# M228pnames.net
KiCad netlist of a schematic drawn in EAGLE
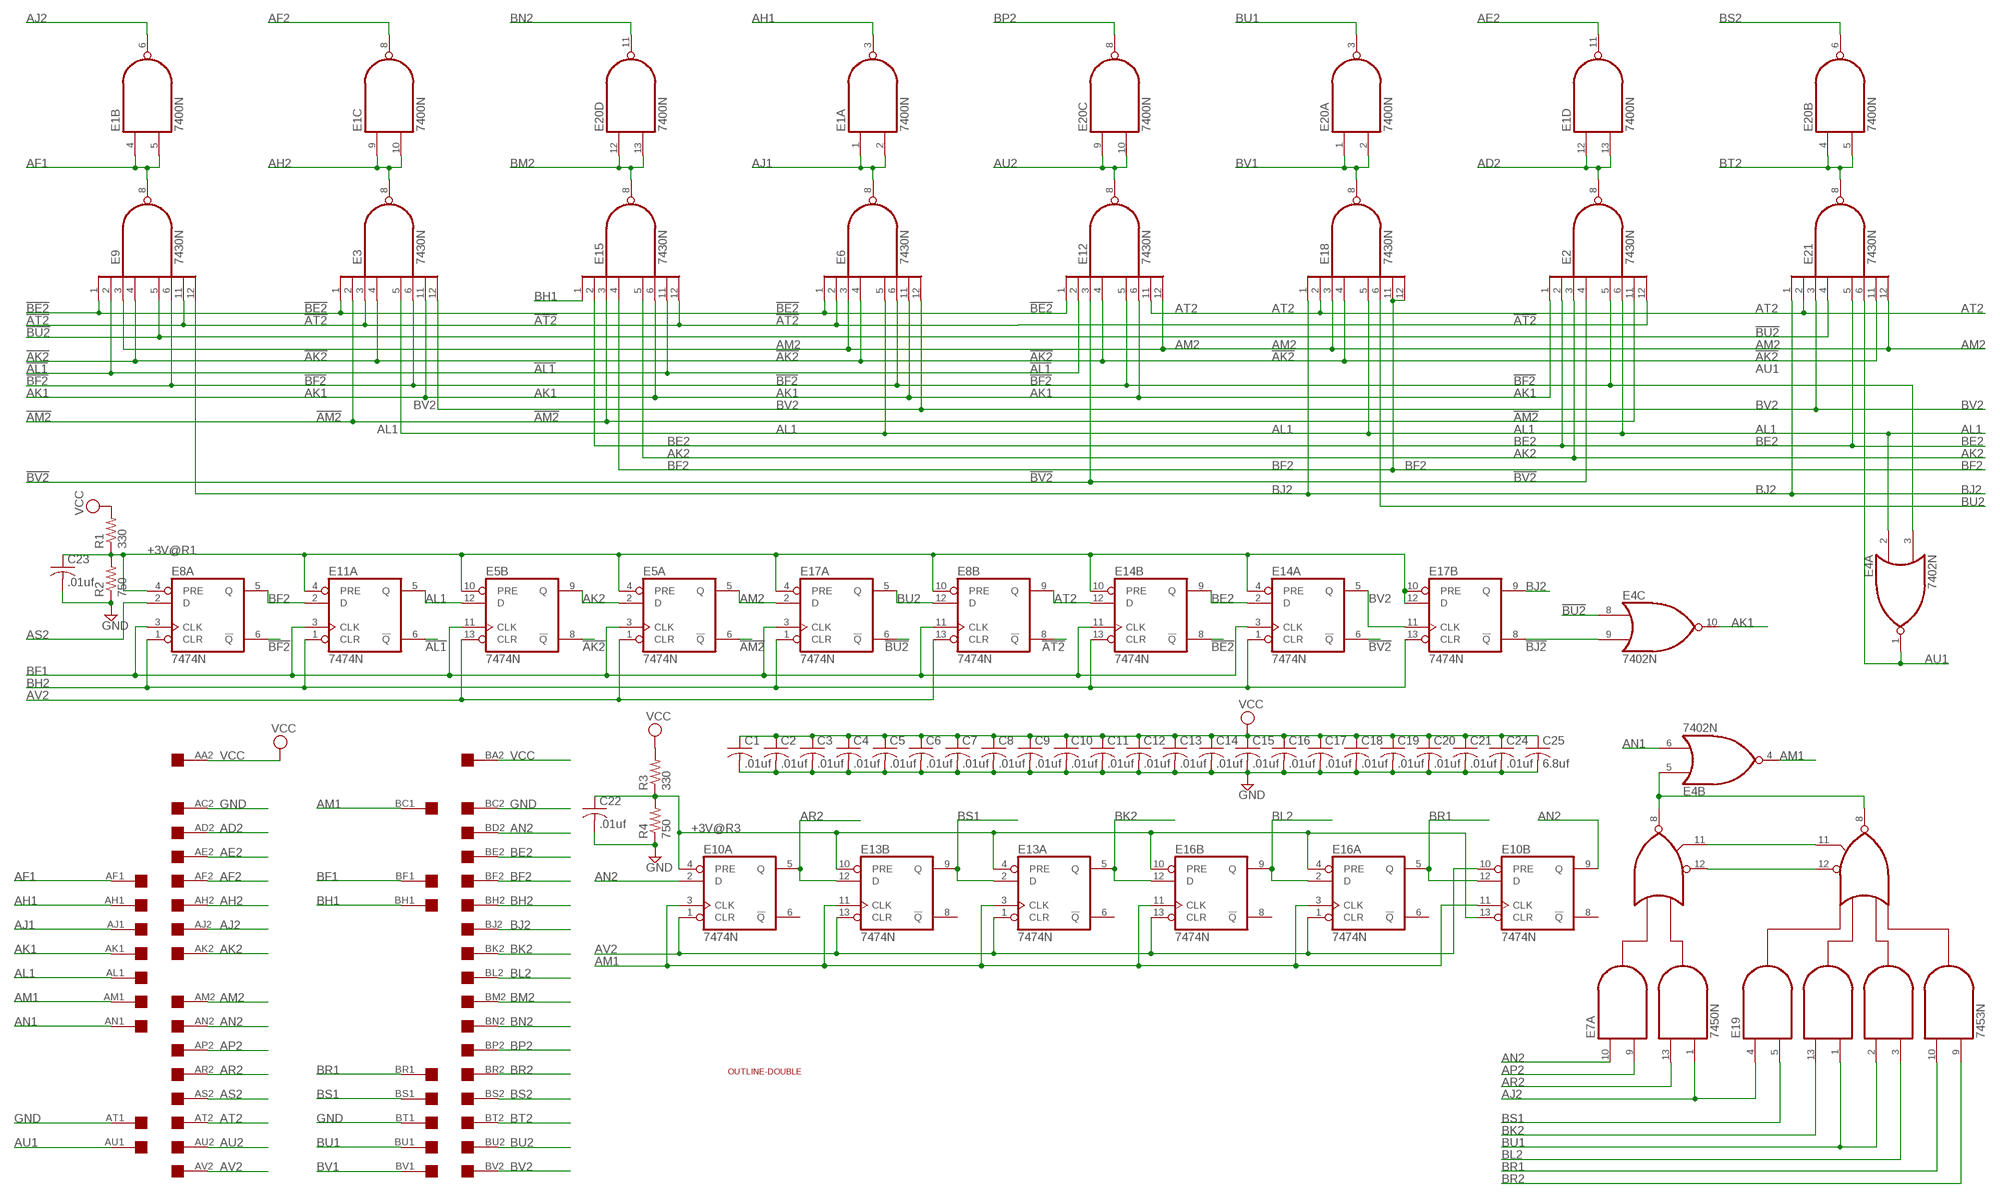
[diagram p0: schematic, sheet 1]

(export (version "E")
  (design (tool "Eeschema 10.0.6"))
  (components
    (comp (ref "C1")
      (value ".01uf")
      (footprint "eagle-import:C050-025X075")
      (libsource (lib "eagle-import") (part "C-US050-025X075"))
    )
    (comp (ref "C2")
      (value ".01uf")
      (footprint "eagle-import:C050-025X075")
      (libsource (lib "eagle-import") (part "C-US050-025X075"))
    )
    (comp (ref "C3")
      (value ".01uf")
      (footprint "eagle-import:C050-025X075")
      (libsource (lib "eagle-import") (part "C-US050-025X075"))
    )
    (comp (ref "C4")
      (value ".01uf")
      (footprint "eagle-import:C050-025X075")
      (libsource (lib "eagle-import") (part "C-US050-025X075"))
    )
    (comp (ref "C5")
      (value ".01uf")
      (footprint "eagle-import:C050-025X075")
      (libsource (lib "eagle-import") (part "C-US050-025X075"))
    )
    (comp (ref "C6")
      (value ".01uf")
      (footprint "eagle-import:C050-025X075")
      (libsource (lib "eagle-import") (part "C-US050-025X075"))
    )
    (comp (ref "C7")
      (value ".01uf")
      (footprint "eagle-import:C050-025X075")
      (libsource (lib "eagle-import") (part "C-US050-025X075"))
    )
    (comp (ref "C8")
      (value ".01uf")
      (footprint "eagle-import:C050-025X075")
      (libsource (lib "eagle-import") (part "C-US050-025X075"))
    )
    (comp (ref "C9")
      (value ".01uf")
      (footprint "eagle-import:C050-025X075")
      (libsource (lib "eagle-import") (part "C-US050-025X075"))
    )
    (comp (ref "C10")
      (value ".01uf")
      (footprint "eagle-import:C050-025X075")
      (libsource (lib "eagle-import") (part "C-US050-025X075"))
    )
    (comp (ref "C11")
      (value ".01uf")
      (footprint "eagle-import:C050-025X075")
      (libsource (lib "eagle-import") (part "C-US050-025X075"))
    )
    (comp (ref "C12")
      (value ".01uf")
      (footprint "eagle-import:C050-025X075")
      (libsource (lib "eagle-import") (part "C-US050-025X075"))
    )
    (comp (ref "C13")
      (value ".01uf")
      (footprint "eagle-import:C050-025X075")
      (libsource (lib "eagle-import") (part "C-US050-025X075"))
    )
    (comp (ref "C14")
      (value ".01uf")
      (footprint "eagle-import:C050-025X075")
      (libsource (lib "eagle-import") (part "C-US050-025X075"))
    )
    (comp (ref "C15")
      (value ".01uf")
      (footprint "eagle-import:C050-025X075")
      (libsource (lib "eagle-import") (part "C-US050-025X075"))
    )
    (comp (ref "C16")
      (value ".01uf")
      (footprint "eagle-import:C050-025X075")
      (libsource (lib "eagle-import") (part "C-US050-025X075"))
    )
    (comp (ref "C17")
      (value ".01uf")
      (footprint "eagle-import:C050-025X075")
      (libsource (lib "eagle-import") (part "C-US050-025X075"))
    )
    (comp (ref "C18")
      (value ".01uf")
      (footprint "eagle-import:C050-025X075")
      (libsource (lib "eagle-import") (part "C-US050-025X075"))
    )
    (comp (ref "C19")
      (value ".01uf")
      (footprint "eagle-import:C050-025X075")
      (libsource (lib "eagle-import") (part "C-US050-025X075"))
    )
    (comp (ref "C20")
      (value ".01uf")
      (footprint "eagle-import:C050-025X075")
      (libsource (lib "eagle-import") (part "C-US050-025X075"))
    )
    (comp (ref "C21")
      (value ".01uf")
      (footprint "eagle-import:C050-025X075")
      (libsource (lib "eagle-import") (part "C-US050-025X075"))
    )
    (comp (ref "C22")
      (value ".01uf")
      (footprint "eagle-import:C050-025X075")
      (libsource (lib "eagle-import") (part "C-US050-025X075"))
    )
    (comp (ref "C23")
      (value ".01uf")
      (footprint "eagle-import:C050-025X075")
      (libsource (lib "eagle-import") (part "C-US050-025X075"))
    )
    (comp (ref "C24")
      (value ".01uf")
      (footprint "eagle-import:C050-025X075")
      (libsource (lib "eagle-import") (part "C-US050-025X075"))
    )
    (comp (ref "C25")
      (value "6.8uf")
      (footprint "eagle-import:C150-054X183")
      (libsource (lib "eagle-import") (part "C-US150-054X183"))
    )
    (comp (ref "E1")
      (value "7400N")
      (footprint "eagle-import:DIL14")
      (libsource (lib "eagle-import") (part "7400N"))
    )
    (comp (ref "E2")
      (value "7430N")
      (footprint "eagle-import:DIL14")
      (libsource (lib "eagle-import") (part "7430N"))
    )
    (comp (ref "E3")
      (value "7430N")
      (footprint "eagle-import:DIL14")
      (libsource (lib "eagle-import") (part "7430N"))
    )
    (comp (ref "E4")
      (value "7402N")
      (footprint "eagle-import:DIL14")
      (libsource (lib "eagle-import") (part "7402N"))
    )
    (comp (ref "E5")
      (value "7474N")
      (footprint "eagle-import:DIL14")
      (libsource (lib "eagle-import") (part "7474NS"))
    )
    (comp (ref "E6")
      (value "7430N")
      (footprint "eagle-import:DIL14")
      (libsource (lib "eagle-import") (part "7430N"))
    )
    (comp (ref "E7")
      (value "7450N")
      (footprint "eagle-import:DIL14")
      (libsource (lib "eagle-import") (part "7450N"))
    )
    (comp (ref "E8")
      (value "7474N")
      (footprint "eagle-import:DIL14")
      (libsource (lib "eagle-import") (part "7474NS"))
    )
    (comp (ref "E9")
      (value "7430N")
      (footprint "eagle-import:DIL14")
      (libsource (lib "eagle-import") (part "7430N"))
    )
    (comp (ref "E10")
      (value "7474N")
      (footprint "eagle-import:DIL14")
      (libsource (lib "eagle-import") (part "7474NS"))
    )
    (comp (ref "E11")
      (value "7474N")
      (footprint "eagle-import:DIL14")
      (libsource (lib "eagle-import") (part "7474NS"))
    )
    (comp (ref "E12")
      (value "7430N")
      (footprint "eagle-import:DIL14")
      (libsource (lib "eagle-import") (part "7430N"))
    )
    (comp (ref "E13")
      (value "7474N")
      (footprint "eagle-import:DIL14")
      (libsource (lib "eagle-import") (part "7474NS"))
    )
    (comp (ref "E14")
      (value "7474N")
      (footprint "eagle-import:DIL14")
      (libsource (lib "eagle-import") (part "7474NS"))
    )
    (comp (ref "E15")
      (value "7430N")
      (footprint "eagle-import:DIL14")
      (libsource (lib "eagle-import") (part "7430N"))
    )
    (comp (ref "E16")
      (value "7474N")
      (footprint "eagle-import:DIL14")
      (libsource (lib "eagle-import") (part "7474NS"))
    )
    (comp (ref "E17")
      (value "7474N")
      (footprint "eagle-import:DIL14")
      (libsource (lib "eagle-import") (part "7474NS"))
    )
    (comp (ref "E18")
      (value "7430N")
      (footprint "eagle-import:DIL14")
      (libsource (lib "eagle-import") (part "7430N"))
    )
    (comp (ref "E19")
      (value "7453N")
      (footprint "eagle-import:DIL14")
      (libsource (lib "eagle-import") (part "7453N"))
    )
    (comp (ref "E20")
      (value "7400N")
      (footprint "eagle-import:DIL14")
      (libsource (lib "eagle-import") (part "7400N"))
    )
    (comp (ref "E21")
      (value "7430N")
      (footprint "eagle-import:DIL14")
      (libsource (lib "eagle-import") (part "7430N"))
    )
    (comp (ref "R1")
      (value "330")
      (footprint "eagle-import:0207_10")
      (libsource (lib "eagle-import") (part "R-US_0207/10"))
    )
    (comp (ref "R2")
      (value "750")
      (footprint "eagle-import:0207_10")
      (libsource (lib "eagle-import") (part "R-US_0207/10"))
    )
    (comp (ref "R3")
      (value "330")
      (footprint "eagle-import:0207_10")
      (libsource (lib "eagle-import") (part "R-US_0207/10"))
    )
    (comp (ref "R4")
      (value "750")
      (footprint "eagle-import:0207_10")
      (libsource (lib "eagle-import") (part "R-US_0207/10"))
    )
    (comp (ref "U$1")
      (value "DOUBLE")
      (footprint "eagle-import:EDGE-CON4")
      (libsource (lib "eagle-import") (part "DOUBLE"))
    )
    (comp (ref "U$2")
      (value "OUTLINE-DOUBLE")
      (footprint "eagle-import:DOUBLE")
      (libsource (lib "eagle-import") (part "OUTLINE-DOUBLE"))
    )
  )
  (nets
    (net (code "1") (name "/+3V@R1") (class "Default")
      (node (ref "C23") (pin "1") (pinfunction "1_1") (pintype "passive"))
      (node (ref "E11") (pin "4") (pinfunction "PRE_4") (pintype "input"))
      (node (ref "E14") (pin "10") (pinfunction "PRE_10") (pintype "input"))
      (node (ref "E14") (pin "4") (pinfunction "PRE_4") (pintype "input"))
      (node (ref "E17") (pin "10") (pinfunction "PRE_10") (pintype "input"))
      (node (ref "E17") (pin "12") (pinfunction "D_12") (pintype "input"))
      (node (ref "E17") (pin "4") (pinfunction "PRE_4") (pintype "input"))
      (node (ref "E5") (pin "10") (pinfunction "PRE_10") (pintype "input"))
      (node (ref "E5") (pin "4") (pinfunction "PRE_4") (pintype "input"))
      (node (ref "E8") (pin "10") (pinfunction "PRE_10") (pintype "input"))
      (node (ref "E8") (pin "4") (pinfunction "PRE_4") (pintype "input"))
      (node (ref "R1") (pin "1") (pinfunction "1_1") (pintype "passive"))
      (node (ref "R2") (pin "2") (pinfunction "2_2") (pintype "passive"))
    )
    (net (code "2") (name "/+3V@R3") (class "Default")
      (node (ref "C22") (pin "1") (pinfunction "1_1") (pintype "passive"))
      (node (ref "E10") (pin "13") (pinfunction "CLR_13") (pintype "input"))
      (node (ref "E10") (pin "4") (pinfunction "PRE_4") (pintype "input"))
      (node (ref "E13") (pin "10") (pinfunction "PRE_10") (pintype "input"))
      (node (ref "E13") (pin "4") (pinfunction "PRE_4") (pintype "input"))
      (node (ref "E16") (pin "10") (pinfunction "PRE_10") (pintype "input"))
      (node (ref "E16") (pin "4") (pinfunction "PRE_4") (pintype "input"))
      (node (ref "R3") (pin "1") (pinfunction "1_1") (pintype "passive"))
      (node (ref "R4") (pin "2") (pinfunction "2_2") (pintype "passive"))
    )
    (net (code "3") (name "/AD2") (class "Default")
      (node (ref "E1") (pin "12") (pinfunction "I0_12") (pintype "input"))
      (node (ref "E1") (pin "13") (pinfunction "I1_13") (pintype "input"))
      (node (ref "E2") (pin "8") (pinfunction "O_8") (pintype "output"))
      (node (ref "U$1") (pin "AD2") (pinfunction "1_AD2") (pintype "bidirectional"))
    )
    (net (code "4") (name "/AE2") (class "Default")
      (node (ref "E1") (pin "11") (pinfunction "O_11") (pintype "output"))
      (node (ref "U$1") (pin "AE2") (pinfunction "1_AE2") (pintype "bidirectional"))
    )
    (net (code "5") (name "/AF1") (class "Default")
      (node (ref "E1") (pin "4") (pinfunction "I0_4") (pintype "input"))
      (node (ref "E1") (pin "5") (pinfunction "I1_5") (pintype "input"))
      (node (ref "E9") (pin "8") (pinfunction "O_8") (pintype "output"))
      (node (ref "U$1") (pin "AF1") (pinfunction "1_AF1") (pintype "bidirectional"))
    )
    (net (code "6") (name "/AF2") (class "Default")
      (node (ref "E1") (pin "8") (pinfunction "O_8") (pintype "output"))
      (node (ref "U$1") (pin "AF2") (pinfunction "1_AF2") (pintype "bidirectional"))
    )
    (net (code "7") (name "/AH1") (class "Default")
      (node (ref "E1") (pin "3") (pinfunction "O_3") (pintype "output"))
      (node (ref "U$1") (pin "AH1") (pinfunction "1_AH1") (pintype "bidirectional"))
    )
    (net (code "8") (name "/AH2") (class "Default")
      (node (ref "E1") (pin "10") (pinfunction "I1_10") (pintype "input"))
      (node (ref "E1") (pin "9") (pinfunction "I0_9") (pintype "input"))
      (node (ref "E3") (pin "8") (pinfunction "O_8") (pintype "output"))
      (node (ref "U$1") (pin "AH2") (pinfunction "1_AH2") (pintype "bidirectional"))
    )
    (net (code "9") (name "/AJ1") (class "Default")
      (node (ref "E1") (pin "1") (pinfunction "I0_1") (pintype "input"))
      (node (ref "E1") (pin "2") (pinfunction "I1_2") (pintype "input"))
      (node (ref "E6") (pin "8") (pinfunction "O_8") (pintype "output"))
      (node (ref "U$1") (pin "AJ1") (pinfunction "1_AJ1") (pintype "bidirectional"))
    )
    (net (code "10") (name "/AJ2") (class "Default")
      (node (ref "E1") (pin "6") (pinfunction "O_6") (pintype "output"))
      (node (ref "E19") (pin "4") (pinfunction "I1_4") (pintype "input"))
      (node (ref "E7") (pin "1") (pinfunction "I4_1") (pintype "input"))
      (node (ref "U$1") (pin "AJ2") (pinfunction "1_AJ2") (pintype "bidirectional"))
    )
    (net (code "11") (name "/AK1") (class "Default")
      (node (ref "E12") (pin "6") (pinfunction "I5_6") (pintype "input"))
      (node (ref "E15") (pin "6") (pinfunction "I5_6") (pintype "input"))
      (node (ref "E2") (pin "1") (pinfunction "I0_1") (pintype "input"))
      (node (ref "E3") (pin "11") (pinfunction "I6_11") (pintype "input"))
      (node (ref "E4") (pin "10") (pinfunction "O_10") (pintype "output"))
      (node (ref "E6") (pin "11") (pinfunction "I6_11") (pintype "input"))
      (node (ref "U$1") (pin "AK1") (pinfunction "1_AK1") (pintype "bidirectional"))
    )
    (net (code "12") (name "/AK2") (class "Default")
      (node (ref "E15") (pin "5") (pinfunction "I4_5") (pintype "input"))
      (node (ref "E2") (pin "3") (pinfunction "I2_3") (pintype "input"))
      (node (ref "E5") (pin "2") (pinfunction "D_2") (pintype "input"))
      (node (ref "E5") (pin "9") (pinfunction "Q_9") (pintype "output"))
      (node (ref "U$1") (pin "AK2") (pinfunction "1_AK2") (pintype "bidirectional"))
    )
    (net (code "13") (name "/AL1") (class "Default")
      (node (ref "E11") (pin "5") (pinfunction "Q_5") (pintype "output"))
      (node (ref "E18") (pin "5") (pinfunction "I4_5") (pintype "input"))
      (node (ref "E2") (pin "6") (pinfunction "I5_6") (pintype "input"))
      (node (ref "E3") (pin "5") (pinfunction "I4_5") (pintype "input"))
      (node (ref "E4") (pin "2") (pinfunction "I0_2") (pintype "input"))
      (node (ref "E5") (pin "12") (pinfunction "D_12") (pintype "input"))
      (node (ref "E6") (pin "5") (pinfunction "I4_5") (pintype "input"))
      (node (ref "U$1") (pin "AL1") (pinfunction "1_AL1") (pintype "bidirectional"))
    )
    (net (code "14") (name "/AM1") (class "Default")
      (node (ref "E10") (pin "11") (pinfunction "CLK_11") (pintype "input"))
      (node (ref "E10") (pin "3") (pinfunction "CLK_3") (pintype "input"))
      (node (ref "E13") (pin "11") (pinfunction "CLK_11") (pintype "input"))
      (node (ref "E13") (pin "3") (pinfunction "CLK_3") (pintype "input"))
      (node (ref "E16") (pin "11") (pinfunction "CLK_11") (pintype "input"))
      (node (ref "E16") (pin "3") (pinfunction "CLK_3") (pintype "input"))
      (node (ref "E4") (pin "4") (pinfunction "O_4") (pintype "output"))
      (node (ref "U$1") (pin "AM1") (pinfunction "1_AM1") (pintype "bidirectional"))
      (node (ref "U$1") (pin "BC1") (pinfunction "1_BC1") (pintype "bidirectional"))
    )
    (net (code "15") (name "/AM2") (class "Default")
      (node (ref "E12") (pin "12") (pinfunction "I7_12") (pintype "input"))
      (node (ref "E17") (pin "2") (pinfunction "D_2") (pintype "input"))
      (node (ref "E18") (pin "3") (pinfunction "I2_3") (pintype "input"))
      (node (ref "E21") (pin "12") (pinfunction "I7_12") (pintype "input"))
      (node (ref "E5") (pin "5") (pinfunction "Q_5") (pintype "output"))
      (node (ref "E6") (pin "3") (pinfunction "I2_3") (pintype "input"))
      (node (ref "E9") (pin "3") (pinfunction "I2_3") (pintype "input"))
      (node (ref "U$1") (pin "AM2") (pinfunction "1_AM2") (pintype "bidirectional"))
    )
    (net (code "16") (name "/AN1") (class "Default")
      (node (ref "E4") (pin "6") (pinfunction "I1_6") (pintype "input"))
      (node (ref "U$1") (pin "AN1") (pinfunction "1_AN1") (pintype "bidirectional"))
    )
    (net (code "17") (name "/AN2") (class "Default")
      (node (ref "E10") (pin "2") (pinfunction "D_2") (pintype "input"))
      (node (ref "E10") (pin "9") (pinfunction "Q_9") (pintype "output"))
      (node (ref "E7") (pin "10") (pinfunction "I1_10") (pintype "input"))
      (node (ref "U$1") (pin "AN2") (pinfunction "1_AN2") (pintype "bidirectional"))
      (node (ref "U$1") (pin "BD2") (pinfunction "1_BD2") (pintype "bidirectional"))
    )
    (net (code "18") (name "/AP2") (class "Default")
      (node (ref "E7") (pin "9") (pinfunction "I2_9") (pintype "input"))
      (node (ref "U$1") (pin "AP2") (pinfunction "1_AP2") (pintype "bidirectional"))
    )
    (net (code "19") (name "/AR2") (class "Default")
      (node (ref "E10") (pin "5") (pinfunction "Q_5") (pintype "output"))
      (node (ref "E13") (pin "12") (pinfunction "D_12") (pintype "input"))
      (node (ref "E7") (pin "13") (pinfunction "I3_13") (pintype "input"))
      (node (ref "U$1") (pin "AR2") (pinfunction "1_AR2") (pintype "bidirectional"))
    )
    (net (code "20") (name "/AS2") (class "Default")
      (node (ref "E8") (pin "2") (pinfunction "D_2") (pintype "input"))
      (node (ref "U$1") (pin "AS2") (pinfunction "1_AS2") (pintype "bidirectional"))
    )
    (net (code "21") (name "/AT2") (class "Default")
      (node (ref "E12") (pin "11") (pinfunction "I6_11") (pintype "input"))
      (node (ref "E14") (pin "12") (pinfunction "D_12") (pintype "input"))
      (node (ref "E18") (pin "2") (pinfunction "I1_2") (pintype "input"))
      (node (ref "E21") (pin "2") (pinfunction "I1_2") (pintype "input"))
      (node (ref "E8") (pin "9") (pinfunction "Q_9") (pintype "output"))
      (node (ref "U$1") (pin "AT2") (pinfunction "1_AT2") (pintype "bidirectional"))
    )
    (net (code "22") (name "/AU1") (class "Default")
      (node (ref "E21") (pin "6") (pinfunction "I5_6") (pintype "input"))
      (node (ref "E4") (pin "1") (pinfunction "O_1") (pintype "output"))
      (node (ref "U$1") (pin "AU1") (pinfunction "1_AU1") (pintype "bidirectional"))
    )
    (net (code "23") (name "/AU2") (class "Default")
      (node (ref "E12") (pin "8") (pinfunction "O_8") (pintype "output"))
      (node (ref "E20") (pin "10") (pinfunction "I1_10") (pintype "input"))
      (node (ref "E20") (pin "9") (pinfunction "I0_9") (pintype "input"))
      (node (ref "U$1") (pin "AU2") (pinfunction "1_AU2") (pintype "bidirectional"))
    )
    (net (code "24") (name "/AV2") (class "Default")
      (node (ref "E10") (pin "1") (pinfunction "CLR_1") (pintype "input"))
      (node (ref "E10") (pin "10") (pinfunction "PRE_10") (pintype "input"))
      (node (ref "E13") (pin "1") (pinfunction "CLR_1") (pintype "input"))
      (node (ref "E13") (pin "13") (pinfunction "CLR_13") (pintype "input"))
      (node (ref "E16") (pin "1") (pinfunction "CLR_1") (pintype "input"))
      (node (ref "E16") (pin "13") (pinfunction "CLR_13") (pintype "input"))
      (node (ref "E5") (pin "1") (pinfunction "CLR_1") (pintype "input"))
      (node (ref "E5") (pin "13") (pinfunction "CLR_13") (pintype "input"))
      (node (ref "E8") (pin "13") (pinfunction "CLR_13") (pintype "input"))
      (node (ref "U$1") (pin "AV2") (pinfunction "1_AV2") (pintype "bidirectional"))
    )
    (net (code "25") (name "/BE2") (class "Default")
      (node (ref "E14") (pin "2") (pinfunction "D_2") (pintype "input"))
      (node (ref "E14") (pin "9") (pinfunction "Q_9") (pintype "output"))
      (node (ref "E15") (pin "2") (pinfunction "I1_2") (pintype "input"))
      (node (ref "E2") (pin "2") (pinfunction "I1_2") (pintype "input"))
      (node (ref "E21") (pin "5") (pinfunction "I4_5") (pintype "input"))
      (node (ref "U$1") (pin "BE2") (pinfunction "1_BE2") (pintype "bidirectional"))
    )
    (net (code "26") (name "/BF1") (class "Default")
      (node (ref "E11") (pin "3") (pinfunction "CLK_3") (pintype "input"))
      (node (ref "E14") (pin "11") (pinfunction "CLK_11") (pintype "input"))
      (node (ref "E14") (pin "3") (pinfunction "CLK_3") (pintype "input"))
      (node (ref "E17") (pin "3") (pinfunction "CLK_3") (pintype "input"))
      (node (ref "E5") (pin "11") (pinfunction "CLK_11") (pintype "input"))
      (node (ref "E5") (pin "3") (pinfunction "CLK_3") (pintype "input"))
      (node (ref "E8") (pin "11") (pinfunction "CLK_11") (pintype "input"))
      (node (ref "E8") (pin "3") (pinfunction "CLK_3") (pintype "input"))
      (node (ref "U$1") (pin "BF1") (pinfunction "1_BF1") (pintype "bidirectional"))
    )
    (net (code "27") (name "/BF2") (class "Default")
      (node (ref "E11") (pin "2") (pinfunction "D_2") (pintype "input"))
      (node (ref "E15") (pin "4") (pinfunction "I3_4") (pintype "input"))
      (node (ref "E18") (pin "11") (pinfunction "I6_11") (pintype "input"))
      (node (ref "E18") (pin "12") (pinfunction "I7_12") (pintype "input"))
      (node (ref "E8") (pin "5") (pinfunction "Q_5") (pintype "output"))
      (node (ref "U$1") (pin "BF2") (pinfunction "1_BF2") (pintype "bidirectional"))
    )
    (net (code "28") (name "/BH1") (class "Default")
      (node (ref "E15") (pin "1") (pinfunction "I0_1") (pintype "input"))
      (node (ref "U$1") (pin "BH1") (pinfunction "1_BH1") (pintype "bidirectional"))
    )
    (net (code "29") (name "/BH2") (class "Default")
      (node (ref "E11") (pin "1") (pinfunction "CLR_1") (pintype "input"))
      (node (ref "E14") (pin "1") (pinfunction "CLR_1") (pintype "input"))
      (node (ref "E14") (pin "13") (pinfunction "CLR_13") (pintype "input"))
      (node (ref "E17") (pin "1") (pinfunction "CLR_1") (pintype "input"))
      (node (ref "E17") (pin "13") (pinfunction "CLR_13") (pintype "input"))
      (node (ref "E8") (pin "1") (pinfunction "CLR_1") (pintype "input"))
      (node (ref "U$1") (pin "BH2") (pinfunction "1_BH2") (pintype "bidirectional"))
    )
    (net (code "30") (name "/BJ2") (class "Default")
      (node (ref "E17") (pin "9") (pinfunction "Q_9") (pintype "output"))
      (node (ref "E18") (pin "1") (pinfunction "I0_1") (pintype "input"))
      (node (ref "E21") (pin "1") (pinfunction "I0_1") (pintype "input"))
      (node (ref "E9") (pin "12") (pinfunction "I7_12") (pintype "input"))
      (node (ref "U$1") (pin "BJ2") (pinfunction "1_BJ2") (pintype "bidirectional"))
    )
    (net (code "31") (name "/BK2") (class "Default")
      (node (ref "E13") (pin "5") (pinfunction "Q_5") (pintype "output"))
      (node (ref "E16") (pin "12") (pinfunction "D_12") (pintype "input"))
      (node (ref "E19") (pin "13") (pinfunction "I3_13") (pintype "input"))
      (node (ref "U$1") (pin "BK2") (pinfunction "1_BK2") (pintype "bidirectional"))
    )
    (net (code "32") (name "/BL2") (class "Default")
      (node (ref "E16") (pin "2") (pinfunction "D_2") (pintype "input"))
      (node (ref "E16") (pin "9") (pinfunction "Q_9") (pintype "output"))
      (node (ref "E19") (pin "3") (pinfunction "I6_3") (pintype "input"))
      (node (ref "U$1") (pin "BL2") (pinfunction "1_BL2") (pintype "bidirectional"))
    )
    (net (code "33") (name "/BM2") (class "Default")
      (node (ref "E15") (pin "8") (pinfunction "O_8") (pintype "output"))
      (node (ref "E20") (pin "12") (pinfunction "I0_12") (pintype "input"))
      (node (ref "E20") (pin "13") (pinfunction "I1_13") (pintype "input"))
      (node (ref "U$1") (pin "BM2") (pinfunction "1_BM2") (pintype "bidirectional"))
    )
    (net (code "34") (name "/BN2") (class "Default")
      (node (ref "E20") (pin "11") (pinfunction "O_11") (pintype "output"))
      (node (ref "U$1") (pin "BN2") (pinfunction "1_BN2") (pintype "bidirectional"))
    )
    (net (code "35") (name "/BP2") (class "Default")
      (node (ref "E20") (pin "8") (pinfunction "O_8") (pintype "output"))
      (node (ref "U$1") (pin "BP2") (pinfunction "1_BP2") (pintype "bidirectional"))
    )
    (net (code "36") (name "/BR1") (class "Default")
      (node (ref "E10") (pin "12") (pinfunction "D_12") (pintype "input"))
      (node (ref "E16") (pin "5") (pinfunction "Q_5") (pintype "output"))
      (node (ref "E19") (pin "10") (pinfunction "I7_10") (pintype "input"))
      (node (ref "U$1") (pin "BR1") (pinfunction "1_BR1") (pintype "bidirectional"))
    )
    (net (code "37") (name "/BR2") (class "Default")
      (node (ref "E19") (pin "9") (pinfunction "I8_9") (pintype "input"))
      (node (ref "U$1") (pin "BR2") (pinfunction "1_BR2") (pintype "bidirectional"))
    )
    (net (code "38") (name "/BS1") (class "Default")
      (node (ref "E13") (pin "2") (pinfunction "D_2") (pintype "input"))
      (node (ref "E13") (pin "9") (pinfunction "Q_9") (pintype "output"))
      (node (ref "E19") (pin "5") (pinfunction "I2_5") (pintype "input"))
      (node (ref "U$1") (pin "BS1") (pinfunction "1_BS1") (pintype "bidirectional"))
    )
    (net (code "39") (name "/BS2") (class "Default")
      (node (ref "E20") (pin "6") (pinfunction "O_6") (pintype "output"))
      (node (ref "U$1") (pin "BS2") (pinfunction "1_BS2") (pintype "bidirectional"))
    )
    (net (code "40") (name "/BT2") (class "Default")
      (node (ref "E20") (pin "4") (pinfunction "I0_4") (pintype "input"))
      (node (ref "E20") (pin "5") (pinfunction "I1_5") (pintype "input"))
      (node (ref "E21") (pin "8") (pinfunction "O_8") (pintype "output"))
      (node (ref "U$1") (pin "BT2") (pinfunction "1_BT2") (pintype "bidirectional"))
    )
    (net (code "41") (name "/BU1") (class "Default")
      (node (ref "E19") (pin "1") (pinfunction "I4_1") (pintype "input"))
      (node (ref "E19") (pin "2") (pinfunction "I5_2") (pintype "input"))
      (node (ref "E20") (pin "3") (pinfunction "O_3") (pintype "output"))
      (node (ref "U$1") (pin "BU1") (pinfunction "1_BU1") (pintype "bidirectional"))
    )
    (net (code "42") (name "/BU2") (class "Default")
      (node (ref "E17") (pin "5") (pinfunction "Q_5") (pintype "output"))
      (node (ref "E18") (pin "6") (pinfunction "I5_6") (pintype "input"))
      (node (ref "E8") (pin "12") (pinfunction "D_12") (pintype "input"))
      (node (ref "U$1") (pin "BU2") (pinfunction "1_BU2") (pintype "bidirectional"))
    )
    (net (code "43") (name "/BV1") (class "Default")
      (node (ref "E18") (pin "8") (pinfunction "O_8") (pintype "output"))
      (node (ref "E20") (pin "1") (pinfunction "I0_1") (pintype "input"))
      (node (ref "E20") (pin "2") (pinfunction "I1_2") (pintype "input"))
      (node (ref "U$1") (pin "BV1") (pinfunction "1_BV1") (pintype "bidirectional"))
    )
    (net (code "44") (name "/BV2") (class "Default")
      (node (ref "E14") (pin "5") (pinfunction "Q_5") (pintype "output"))
      (node (ref "E17") (pin "11") (pinfunction "CLK_11") (pintype "input"))
      (node (ref "E21") (pin "3") (pinfunction "I2_3") (pintype "input"))
      (node (ref "E3") (pin "12") (pinfunction "I7_12") (pintype "input"))
      (node (ref "E6") (pin "12") (pinfunction "I7_12") (pintype "input"))
      (node (ref "U$1") (pin "BV2") (pinfunction "1_BV2") (pintype "bidirectional"))
    )
    (net (code "45") (name "/~{AK2}") (class "Default")
      (node (ref "E12") (pin "4") (pinfunction "I3_4") (pintype "input"))
      (node (ref "E18") (pin "4") (pinfunction "I3_4") (pintype "input"))
      (node (ref "E21") (pin "11") (pinfunction "I6_11") (pintype "input"))
      (node (ref "E3") (pin "4") (pinfunction "I3_4") (pintype "input"))
      (node (ref "E5") (pin "8") (pinfunction "~{Q}_8") (pintype "output"))
      (node (ref "E6") (pin "4") (pinfunction "I3_4") (pintype "input"))
      (node (ref "E9") (pin "4") (pinfunction "I3_4") (pintype "input"))
    )
    (net (code "46") (name "/~{AL1}") (class "Default")
      (node (ref "E11") (pin "6") (pinfunction "~{Q}_6") (pintype "output"))
      (node (ref "E12") (pin "2") (pinfunction "I1_2") (pintype "input"))
      (node (ref "E15") (pin "11") (pinfunction "I6_11") (pintype "input"))
      (node (ref "E9") (pin "2") (pinfunction "I1_2") (pintype "input"))
    )
    (net (code "47") (name "/~{AM2}") (class "Default")
      (node (ref "E15") (pin "3") (pinfunction "I2_3") (pintype "input"))
      (node (ref "E2") (pin "11") (pinfunction "I6_11") (pintype "input"))
      (node (ref "E3") (pin "2") (pinfunction "I1_2") (pintype "input"))
      (node (ref "E5") (pin "6") (pinfunction "~{Q}_6") (pintype "output"))
    )
    (net (code "48") (name "/~{AT2}") (class "Default")
      (node (ref "E15") (pin "12") (pinfunction "I7_12") (pintype "input"))
      (node (ref "E2") (pin "12") (pinfunction "I7_12") (pintype "input"))
      (node (ref "E3") (pin "3") (pinfunction "I2_3") (pintype "input"))
      (node (ref "E6") (pin "2") (pinfunction "I1_2") (pintype "input"))
      (node (ref "E8") (pin "8") (pinfunction "~{Q}_8") (pintype "output"))
      (node (ref "E9") (pin "11") (pinfunction "I6_11") (pintype "input"))
    )
    (net (code "49") (name "/~{BE2}") (class "Default")
      (node (ref "E12") (pin "1") (pinfunction "I0_1") (pintype "input"))
      (node (ref "E14") (pin "8") (pinfunction "~{Q}_8") (pintype "output"))
      (node (ref "E3") (pin "1") (pinfunction "I0_1") (pintype "input"))
      (node (ref "E6") (pin "1") (pinfunction "I0_1") (pintype "input"))
      (node (ref "E9") (pin "1") (pinfunction "I0_1") (pintype "input"))
    )
    (net (code "50") (name "/~{BF2}") (class "Default")
      (node (ref "E12") (pin "5") (pinfunction "I4_5") (pintype "input"))
      (node (ref "E2") (pin "5") (pinfunction "I4_5") (pintype "input"))
      (node (ref "E3") (pin "6") (pinfunction "I5_6") (pintype "input"))
      (node (ref "E4") (pin "3") (pinfunction "I1_3") (pintype "input"))
      (node (ref "E6") (pin "6") (pinfunction "I5_6") (pintype "input"))
      (node (ref "E8") (pin "6") (pinfunction "~{Q}_6") (pintype "output"))
      (node (ref "E9") (pin "6") (pinfunction "I5_6") (pintype "input"))
    )
    (net (code "51") (name "/~{BJ2}") (class "Default")
      (node (ref "E17") (pin "8") (pinfunction "~{Q}_8") (pintype "output"))
      (node (ref "E4") (pin "9") (pinfunction "I1_9") (pintype "input"))
    )
    (net (code "52") (name "/~{BU2}") (class "Default")
      (node (ref "E17") (pin "6") (pinfunction "~{Q}_6") (pintype "output"))
      (node (ref "E21") (pin "4") (pinfunction "I3_4") (pintype "input"))
      (node (ref "E4") (pin "8") (pinfunction "I0_8") (pintype "input"))
      (node (ref "E9") (pin "5") (pinfunction "I4_5") (pintype "input"))
    )
    (net (code "53") (name "/~{BV2}") (class "Default")
      (node (ref "E12") (pin "3") (pinfunction "I2_3") (pintype "input"))
      (node (ref "E14") (pin "6") (pinfunction "~{Q}_6") (pintype "output"))
      (node (ref "E2") (pin "4") (pinfunction "I3_4") (pintype "input"))
    )
    (net (code "54") (name "GND") (class "Default")
      (node (ref "C1") (pin "2") (pinfunction "2_2") (pintype "passive"))
      (node (ref "C10") (pin "2") (pinfunction "2_2") (pintype "passive"))
      (node (ref "C11") (pin "2") (pinfunction "2_2") (pintype "passive"))
      (node (ref "C12") (pin "2") (pinfunction "2_2") (pintype "passive"))
      (node (ref "C13") (pin "2") (pinfunction "2_2") (pintype "passive"))
      (node (ref "C14") (pin "2") (pinfunction "2_2") (pintype "passive"))
      (node (ref "C15") (pin "2") (pinfunction "2_2") (pintype "passive"))
      (node (ref "C16") (pin "2") (pinfunction "2_2") (pintype "passive"))
      (node (ref "C17") (pin "2") (pinfunction "2_2") (pintype "passive"))
      (node (ref "C18") (pin "2") (pinfunction "2_2") (pintype "passive"))
      (node (ref "C19") (pin "2") (pinfunction "2_2") (pintype "passive"))
      (node (ref "C2") (pin "2") (pinfunction "2_2") (pintype "passive"))
      (node (ref "C20") (pin "2") (pinfunction "2_2") (pintype "passive"))
      (node (ref "C21") (pin "2") (pinfunction "2_2") (pintype "passive"))
      (node (ref "C22") (pin "2") (pinfunction "2_2") (pintype "passive"))
      (node (ref "C23") (pin "2") (pinfunction "2_2") (pintype "passive"))
      (node (ref "C24") (pin "2") (pinfunction "2_2") (pintype "passive"))
      (node (ref "C25") (pin "2") (pinfunction "2_2") (pintype "passive"))
      (node (ref "C3") (pin "2") (pinfunction "2_2") (pintype "passive"))
      (node (ref "C4") (pin "2") (pinfunction "2_2") (pintype "passive"))
      (node (ref "C5") (pin "2") (pinfunction "2_2") (pintype "passive"))
      (node (ref "C6") (pin "2") (pinfunction "2_2") (pintype "passive"))
      (node (ref "C7") (pin "2") (pinfunction "2_2") (pintype "passive"))
      (node (ref "C8") (pin "2") (pinfunction "2_2") (pintype "passive"))
      (node (ref "C9") (pin "2") (pinfunction "2_2") (pintype "passive"))
      (node (ref "R2") (pin "1") (pinfunction "1_1") (pintype "passive"))
      (node (ref "R4") (pin "1") (pinfunction "1_1") (pintype "passive"))
      (node (ref "U$1") (pin "AC2") (pinfunction "1_AC2") (pintype "bidirectional"))
      (node (ref "U$1") (pin "AT1") (pinfunction "1_AT1") (pintype "bidirectional"))
      (node (ref "U$1") (pin "BC2") (pinfunction "1_BC2") (pintype "bidirectional"))
      (node (ref "U$1") (pin "BT1") (pinfunction "1_BT1") (pintype "bidirectional"))
    )
    (net (code "55") (name "Net-(E19A-I9)") (class "Default")
      (node (ref "E19") (pin "12") (pinfunction "I9_12") (pintype "passive"))
      (node (ref "E7") (pin "12") (pinfunction "I5_12") (pintype "passive"))
    )
    (net (code "56") (name "Net-(E19A-I10)") (class "Default")
      (node (ref "E19") (pin "11") (pinfunction "I10_11") (pintype "passive"))
      (node (ref "E7") (pin "11") (pinfunction "I6_11") (pintype "passive"))
    )
    (net (code "57") (name "Net-(E19A-O)") (class "Default")
      (node (ref "E19") (pin "8") (pinfunction "O_8") (pintype "output"))
      (node (ref "E4") (pin "5") (pinfunction "I0_5") (pintype "input"))
      (node (ref "E7") (pin "8") (pinfunction "O_8") (pintype "output"))
    )
    (net (code "58") (name "VCC") (class "Default")
      (node (ref "C1") (pin "1") (pinfunction "1_1") (pintype "passive"))
      (node (ref "C10") (pin "1") (pinfunction "1_1") (pintype "passive"))
      (node (ref "C11") (pin "1") (pinfunction "1_1") (pintype "passive"))
      (node (ref "C12") (pin "1") (pinfunction "1_1") (pintype "passive"))
      (node (ref "C13") (pin "1") (pinfunction "1_1") (pintype "passive"))
      (node (ref "C14") (pin "1") (pinfunction "1_1") (pintype "passive"))
      (node (ref "C15") (pin "1") (pinfunction "1_1") (pintype "passive"))
      (node (ref "C16") (pin "1") (pinfunction "1_1") (pintype "passive"))
      (node (ref "C17") (pin "1") (pinfunction "1_1") (pintype "passive"))
      (node (ref "C18") (pin "1") (pinfunction "1_1") (pintype "passive"))
      (node (ref "C19") (pin "1") (pinfunction "1_1") (pintype "passive"))
      (node (ref "C2") (pin "1") (pinfunction "1_1") (pintype "passive"))
      (node (ref "C20") (pin "1") (pinfunction "1_1") (pintype "passive"))
      (node (ref "C21") (pin "1") (pinfunction "1_1") (pintype "passive"))
      (node (ref "C24") (pin "1") (pinfunction "1_1") (pintype "passive"))
      (node (ref "C25") (pin "1") (pinfunction "1_1") (pintype "passive"))
      (node (ref "C3") (pin "1") (pinfunction "1_1") (pintype "passive"))
      (node (ref "C4") (pin "1") (pinfunction "1_1") (pintype "passive"))
      (node (ref "C5") (pin "1") (pinfunction "1_1") (pintype "passive"))
      (node (ref "C6") (pin "1") (pinfunction "1_1") (pintype "passive"))
      (node (ref "C7") (pin "1") (pinfunction "1_1") (pintype "passive"))
      (node (ref "C8") (pin "1") (pinfunction "1_1") (pintype "passive"))
      (node (ref "C9") (pin "1") (pinfunction "1_1") (pintype "passive"))
      (node (ref "R1") (pin "2") (pinfunction "2_2") (pintype "passive"))
      (node (ref "R3") (pin "2") (pinfunction "2_2") (pintype "passive"))
      (node (ref "U$1") (pin "AA2") (pinfunction "1_AA2") (pintype "bidirectional"))
      (node (ref "U$1") (pin "BA2") (pinfunction "1_BA2") (pintype "bidirectional"))
    )
    (net (code "59") (name "unconnected-(E10A-~{Q}-Pad6)") (class "Default")
      (node (ref "E10") (pin "6") (pinfunction "~{Q}_6") (pintype "output"))
    )
    (net (code "60") (name "unconnected-(E10B-~{Q}-Pad8)") (class "Default")
      (node (ref "E10") (pin "8") (pinfunction "~{Q}_8") (pintype "output"))
    )
    (net (code "61") (name "unconnected-(E13A-~{Q}-Pad6)") (class "Default")
      (node (ref "E13") (pin "6") (pinfunction "~{Q}_6") (pintype "output"))
    )
    (net (code "62") (name "unconnected-(E13B-~{Q}-Pad8)") (class "Default")
      (node (ref "E13") (pin "8") (pinfunction "~{Q}_8") (pintype "output"))
    )
    (net (code "63") (name "unconnected-(E16A-~{Q}-Pad6)") (class "Default")
      (node (ref "E16") (pin "6") (pinfunction "~{Q}_6") (pintype "output"))
    )
    (net (code "64") (name "unconnected-(E16B-~{Q}-Pad8)") (class "Default")
      (node (ref "E16") (pin "8") (pinfunction "~{Q}_8") (pintype "output"))
    )
  )
)
